# sp_na.net
KiCad netlist of a schematic drawn in EAGLE
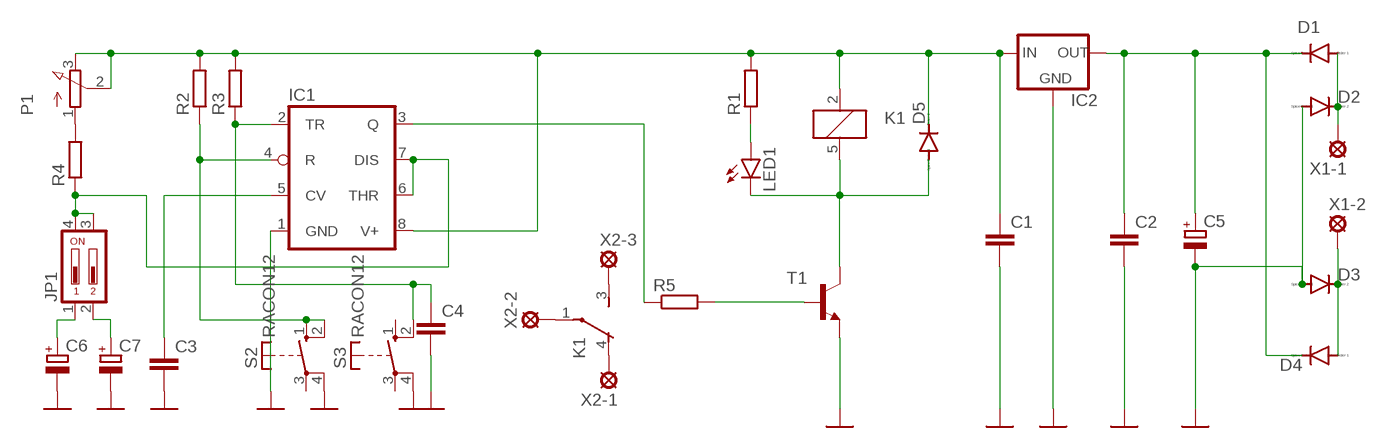
[diagram p0: schematic, sheet 1]

(export (version "E")
  (design (tool "Eeschema 10.0.6"))
  (components
    (comp (ref "C1")
      (value "C-EU025-030X050")
      (footprint "eagle-import:C025-030X050")
      (libsource (lib "eagle-import") (part "C-EU025-030X050"))
    )
    (comp (ref "C2")
      (value "C-EU025-030X050")
      (footprint "eagle-import:C025-030X050")
      (libsource (lib "eagle-import") (part "C-EU025-030X050"))
    )
    (comp (ref "C3")
      (value "C-EU025-030X050")
      (footprint "eagle-import:C025-030X050")
      (libsource (lib "eagle-import") (part "C-EU025-030X050"))
    )
    (comp (ref "C4")
      (value "C-EU025-030X050")
      (footprint "eagle-import:C025-030X050")
      (libsource (lib "eagle-import") (part "C-EU025-030X050"))
    )
    (comp (ref "C5")
      (value "CPOL-EUB45181B")
      (footprint "eagle-import:B45181B")
      (libsource (lib "eagle-import") (part "CPOL-EUB45181B"))
    )
    (comp (ref "C6")
      (value "CPOL-EUB45181B")
      (footprint "eagle-import:B45181B")
      (libsource (lib "eagle-import") (part "CPOL-EUB45181B"))
    )
    (comp (ref "C7")
      (value "CPOL-EUB45181B")
      (footprint "eagle-import:B45181B")
      (libsource (lib "eagle-import") (part "CPOL-EUB45181B"))
    )
    (comp (ref "D1")
      (value "1N4004")
      (footprint "eagle-import:DO41-10")
      (libsource (lib "eagle-import") (part "1N4004"))
    )
    (comp (ref "D2")
      (value "1N4004")
      (footprint "eagle-import:DO41-10")
      (libsource (lib "eagle-import") (part "1N4004"))
    )
    (comp (ref "D3")
      (value "1N4004")
      (footprint "eagle-import:DO41-10")
      (libsource (lib "eagle-import") (part "1N4004"))
    )
    (comp (ref "D4")
      (value "1N4004")
      (footprint "eagle-import:DO41-10")
      (libsource (lib "eagle-import") (part "1N4004"))
    )
    (comp (ref "D5")
      (value "1N4004")
      (footprint "eagle-import:DO41-10")
      (libsource (lib "eagle-import") (part "1N4004"))
    )
    (comp (ref "IC1")
      (value "LM555N")
      (footprint "eagle-import:DIL08")
      (libsource (lib "eagle-import") (part "555NLM"))
    )
    (comp (ref "IC2")
      (value "78XXL")
      (footprint "eagle-import:78XXL")
      (libsource (lib "eagle-import") (part "78XXL"))
    )
    (comp (ref "JP1")
      (value "219-02J")
      (footprint "eagle-import:CTS-219-02J")
      (libsource (lib "eagle-import") (part "219-02J"))
    )
    (comp (ref "K1")
      (value "AZ8-FORM-C")
      (footprint "eagle-import:AZ8")
      (libsource (lib "eagle-import") (part "AZ8-FORM-C"))
    )
    (comp (ref "LED1")
      (value "TLLR4400")
      (footprint "eagle-import:LED3MM")
      (fields (field (name "MF") "VISHAY SEMICONDUCTOR"))
      (libsource (lib "eagle-import") (part "TLLR4400"))
    )
    (comp (ref "P1")
      (value "3RP/1610N")
      (footprint "eagle-import:3RP_1610N")
      (libsource (lib "eagle-import") (part "3RP/1610N"))
    )
    (comp (ref "R1")
      (value "R-EU_0207/10")
      (footprint "eagle-import:0207_10")
      (libsource (lib "eagle-import") (part "R-EU_0207/10"))
    )
    (comp (ref "R2")
      (value "R-EU_0207/10")
      (footprint "eagle-import:0207_10")
      (libsource (lib "eagle-import") (part "R-EU_0207/10"))
    )
    (comp (ref "R3")
      (value "R-EU_0207/10")
      (footprint "eagle-import:0207_10")
      (libsource (lib "eagle-import") (part "R-EU_0207/10"))
    )
    (comp (ref "R4")
      (value "R-EU_0207/10")
      (footprint "eagle-import:0207_10")
      (libsource (lib "eagle-import") (part "R-EU_0207/10"))
    )
    (comp (ref "R5")
      (value "R-EU_0207/10")
      (footprint "eagle-import:0207_10")
      (libsource (lib "eagle-import") (part "R-EU_0207/10"))
    )
    (comp (ref "S2")
      (value "RACON12")
      (footprint "eagle-import:RACON12")
      (libsource (lib "eagle-import") (part "RACON12"))
    )
    (comp (ref "S3")
      (value "RACON12")
      (footprint "eagle-import:RACON12")
      (libsource (lib "eagle-import") (part "RACON12"))
    )
    (comp (ref "T1")
      (value "2N3565")
      (footprint "eagle-import:TO92")
      (libsource (lib "eagle-import") (part "2N3565"))
    )
    (comp (ref "X1-1")
      (value "SE14")
      (footprint "eagle-import:SE14")
      (libsource (lib "eagle-import") (part "SE14"))
    )
    (comp (ref "X1-2")
      (value "SE14")
      (footprint "eagle-import:SE14")
      (libsource (lib "eagle-import") (part "SE14"))
    )
    (comp (ref "X2-1")
      (value "SE14")
      (footprint "eagle-import:SE14")
      (libsource (lib "eagle-import") (part "SE14"))
    )
    (comp (ref "X2-2")
      (value "SE14")
      (footprint "eagle-import:SE14")
      (libsource (lib "eagle-import") (part "SE14"))
    )
    (comp (ref "X2-3")
      (value "SE14")
      (footprint "eagle-import:SE14")
      (libsource (lib "eagle-import") (part "SE14"))
    )
  )
  (nets
    (net (code "1") (name "GND") (class "Default")
      (node (ref "C1") (pin "2") (pinfunction "2_2") (pintype "passive"))
      (node (ref "C2") (pin "2") (pinfunction "2_2") (pintype "passive"))
      (node (ref "C3") (pin "2") (pinfunction "2_2") (pintype "passive"))
      (node (ref "C4") (pin "2") (pinfunction "2_2") (pintype "passive"))
      (node (ref "C5") (pin "-") (pinfunction "-_-") (pintype "passive"))
      (node (ref "C6") (pin "-") (pinfunction "-_-") (pintype "passive"))
      (node (ref "C7") (pin "-") (pinfunction "-_-") (pintype "passive"))
      (node (ref "D2") (pin "A") (pinfunction "A_A") (pintype "passive"))
      (node (ref "D3") (pin "A") (pinfunction "A_A") (pintype "passive"))
      (node (ref "IC1") (pin "1") (pinfunction "GND_1") (pintype "power_in"))
      (node (ref "IC2") (pin "GND") (pinfunction "GND_GND") (pintype "input"))
      (node (ref "S2") (pin "4") (pinfunction "P_4") (pintype "passive"))
      (node (ref "S3") (pin "4") (pinfunction "P_4") (pintype "passive"))
      (node (ref "T1") (pin "3") (pinfunction "E_3") (pintype "passive"))
    )
    (net (code "2") (name "Net-(C2-Pad1)") (class "Default")
      (node (ref "C2") (pin "1") (pinfunction "1_1") (pintype "passive"))
      (node (ref "C5") (pin "+") (pinfunction "+_+") (pintype "passive"))
      (node (ref "D1") (pin "C") (pinfunction "C_C") (pintype "passive"))
      (node (ref "D4") (pin "C") (pinfunction "C_C") (pintype "passive"))
      (node (ref "IC2") (pin "OUT") (pinfunction "OUT_OUT") (pintype "passive"))
    )
    (net (code "3") (name "Net-(C6-Pad+)") (class "Default")
      (node (ref "C6") (pin "+") (pinfunction "+_+") (pintype "passive"))
      (node (ref "JP1") (pin "1") (pinfunction "1_1") (pintype "passive"))
    )
    (net (code "4") (name "Net-(C7-Pad+)") (class "Default")
      (node (ref "C7") (pin "+") (pinfunction "+_+") (pintype "passive"))
      (node (ref "JP1") (pin "2") (pinfunction "2_2") (pintype "passive"))
    )
    (net (code "5") (name "Net-(D1-PadA)") (class "Default")
      (node (ref "D1") (pin "A") (pinfunction "A_A") (pintype "passive"))
      (node (ref "D2") (pin "C") (pinfunction "C_C") (pintype "passive"))
      (node (ref "X1-1") (pin "MP") (pinfunction "MP_MP") (pintype "passive"))
    )
    (net (code "6") (name "Net-(D3-PadC)") (class "Default")
      (node (ref "D3") (pin "C") (pinfunction "C_C") (pintype "passive"))
      (node (ref "D4") (pin "A") (pinfunction "A_A") (pintype "passive"))
      (node (ref "X1-2") (pin "MP") (pinfunction "MP_MP") (pintype "passive"))
    )
    (net (code "7") (name "Net-(IC1-CV)") (class "Default")
      (node (ref "C3") (pin "1") (pinfunction "1_1") (pintype "passive"))
      (node (ref "IC1") (pin "5") (pinfunction "CV_5") (pintype "input"))
    )
    (net (code "8") (name "Net-(IC1-DIS)") (class "Default")
      (node (ref "IC1") (pin "6") (pinfunction "THR_6") (pintype "input"))
      (node (ref "IC1") (pin "7") (pinfunction "DIS_7") (pintype "input"))
      (node (ref "JP1") (pin "3") (pinfunction "3_3") (pintype "passive"))
      (node (ref "JP1") (pin "4") (pinfunction "4_4") (pintype "passive"))
      (node (ref "R4") (pin "1") (pinfunction "1_1") (pintype "passive"))
    )
    (net (code "9") (name "Net-(IC1-Q)") (class "Default")
      (node (ref "IC1") (pin "3") (pinfunction "Q_3") (pintype "output"))
      (node (ref "R5") (pin "1") (pinfunction "1_1") (pintype "passive"))
    )
    (net (code "10") (name "Net-(IC1-R)") (class "Default")
      (node (ref "IC1") (pin "4") (pinfunction "R_4") (pintype "input"))
      (node (ref "R2") (pin "1") (pinfunction "1_1") (pintype "passive"))
      (node (ref "S2") (pin "1") (pinfunction "S_1") (pintype "passive"))
      (node (ref "S2") (pin "2") (pinfunction "S_2") (pintype "passive"))
    )
    (net (code "11") (name "Net-(IC1-TR)") (class "Default")
      (node (ref "C4") (pin "1") (pinfunction "1_1") (pintype "passive"))
      (node (ref "IC1") (pin "2") (pinfunction "TR_2") (pintype "input"))
      (node (ref "R3") (pin "1") (pinfunction "1_1") (pintype "passive"))
      (node (ref "S3") (pin "2") (pinfunction "S_2") (pintype "passive"))
    )
    (net (code "12") (name "Net-(IC1-V+)") (class "Default")
      (node (ref "C1") (pin "1") (pinfunction "1_1") (pintype "passive"))
      (node (ref "D5") (pin "C") (pinfunction "C_C") (pintype "passive"))
      (node (ref "IC1") (pin "8") (pinfunction "V+_8") (pintype "power_in"))
      (node (ref "IC2") (pin "IN") (pinfunction "IN_IN") (pintype "input"))
      (node (ref "K1") (pin "2") (pinfunction "1_2") (pintype "passive"))
      (node (ref "P1") (pin "2") (pinfunction "S_2") (pintype "passive"))
      (node (ref "P1") (pin "3") (pinfunction "E_3") (pintype "passive"))
      (node (ref "R1") (pin "2") (pinfunction "2_2") (pintype "passive"))
      (node (ref "R2") (pin "2") (pinfunction "2_2") (pintype "passive"))
      (node (ref "R3") (pin "2") (pinfunction "2_2") (pintype "passive"))
    )
    (net (code "13") (name "Net-(K1A-O)") (class "Default")
      (node (ref "K1") (pin "4") (pinfunction "O_4") (pintype "passive"))
      (node (ref "X2-1") (pin "MP") (pinfunction "MP_MP") (pintype "passive"))
    )
    (net (code "14") (name "Net-(K1A-P)") (class "Default")
      (node (ref "K1") (pin "1") (pinfunction "P_1") (pintype "passive"))
      (node (ref "X2-2") (pin "MP") (pinfunction "MP_MP") (pintype "passive"))
    )
    (net (code "15") (name "Net-(K1A-S)") (class "Default")
      (node (ref "K1") (pin "3") (pinfunction "S_3") (pintype "passive"))
      (node (ref "X2-3") (pin "MP") (pinfunction "MP_MP") (pintype "passive"))
    )
    (net (code "16") (name "Net-(K1B-2)") (class "Default")
      (node (ref "D5") (pin "A") (pinfunction "A_A") (pintype "passive"))
      (node (ref "K1") (pin "5") (pinfunction "2_5") (pintype "passive"))
      (node (ref "LED1") (pin "K") (pinfunction "C_K") (pintype "passive"))
      (node (ref "T1") (pin "1") (pinfunction "C_1") (pintype "passive"))
    )
    (net (code "17") (name "Net-(LED1-PadA)") (class "Default")
      (node (ref "LED1") (pin "A") (pinfunction "A_A") (pintype "passive"))
      (node (ref "R1") (pin "1") (pinfunction "1_1") (pintype "passive"))
    )
    (net (code "18") (name "Net-(P1-A)") (class "Default")
      (node (ref "P1") (pin "1") (pinfunction "A_1") (pintype "passive"))
      (node (ref "R4") (pin "2") (pinfunction "2_2") (pintype "passive"))
    )
    (net (code "19") (name "Net-(T1-B)") (class "Default")
      (node (ref "R5") (pin "2") (pinfunction "2_2") (pintype "passive"))
      (node (ref "T1") (pin "2") (pinfunction "B_2") (pintype "passive"))
    )
    (net (code "20") (name "unconnected-(S2-P-Pad3)") (class "Default")
      (node (ref "S2") (pin "3") (pinfunction "P_3") (pintype "passive"))
    )
    (net (code "21") (name "unconnected-(S3-P-Pad3)") (class "Default")
      (node (ref "S3") (pin "3") (pinfunction "P_3") (pintype "passive"))
    )
    (net (code "22") (name "unconnected-(S3-S-Pad1)") (class "Default")
      (node (ref "S3") (pin "1") (pinfunction "S_1") (pintype "passive"))
    )
  )
)
